# CorrosenseBoard_V4_2.net
KiCad netlist of a schematic drawn in Altium Designer
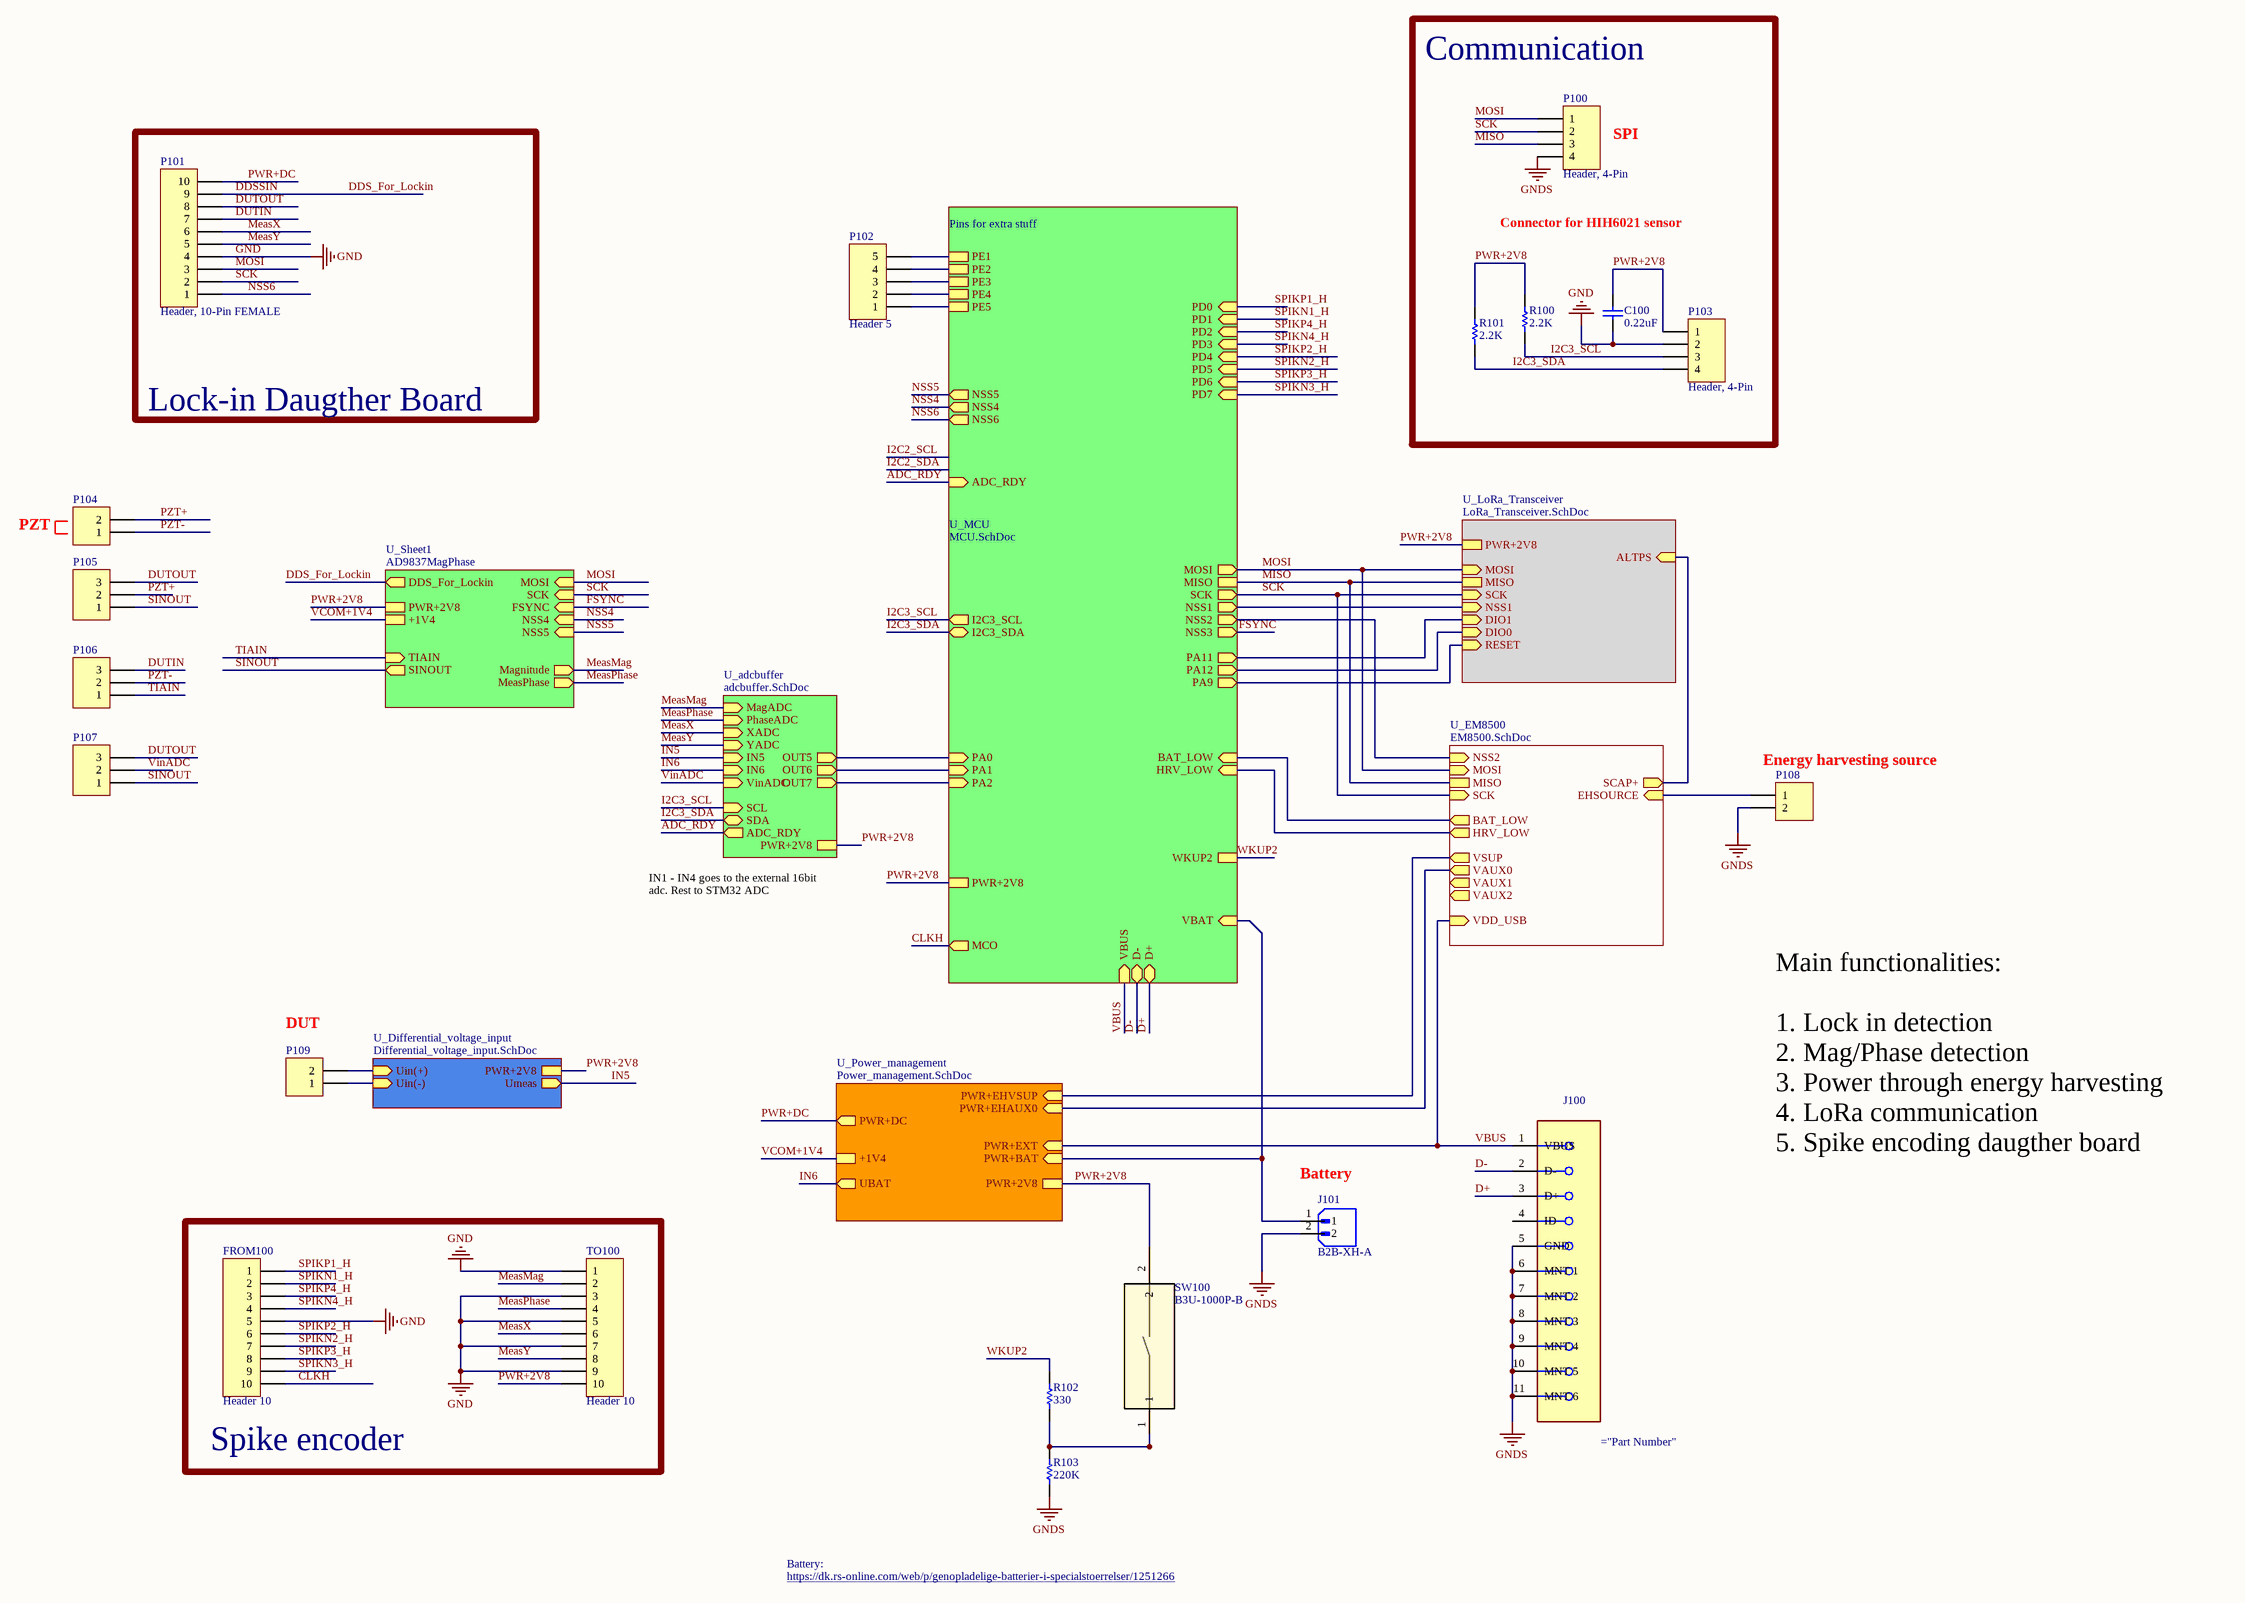
[diagram p0: CorrosenseBoard_V4.2.SchDoc]

(export (version "E")
  (design (tool "Eeschema 10.0.6"))
  (components
    (comp (ref "C100")
      (value "0.22uF")
      (footprint "1608[0603]")
      (description "CAP CER 25V X7R 0603")
      (fields (field (name "TOLERANCE") "±10%") (field (name "MANUFACTURER") "Murata Electronics"))
      (libsource (lib "Miscellaneous Devices") (part "Cap"))
    )
    (comp (ref "FROM100")
      (value "Header 10")
      (footprint "HDR1X10")
      (description "Header, 10-Pin")
      (fields
        (field (name "MANUFACTURER") "Wurth Elektronik")
        (field (name "MPN") "61301011121")
        (field (name "PUBLISHER") "Altium Limited")
      )
      (libsource (lib "") (part "Header 10_1"))
    )
    (comp (ref "J100")
      (value "0473460001")
      (footprint "Molex_0473460001_0")
      (description "USB Connectors MICRO USB B RECPT BTTM MOUNT ASSY")
      (fields (field (name "MANUFACTURER") "Molex"))
      (libsource (lib "Conn_Molex_0473460001_eec") (part "0473460001"))
    )
    (comp (ref "J101")
      (value "B2B-XH-A")
      (footprint "JST_B2B-XH-A")
      (description "B2B-XH-A(LF)(SN)")
      (fields
        (field (name "MF") "{'manufacturer': u'JST Sales America Inc.'}")
        (field (name "MANUFACTURER") "JST Commercial")
      )
      (libsource (lib "B2B-XH-A") (part "B2B-XH-A"))
    )
    (comp (ref "P100")
      (value "Header, 4-Pin")
      (footprint "HDR1X4")
      (fields
        (field (name "MANUFACTURER") "Würth Elektronik")
        (field (name "MPN") "61300411121")
        (field (name "PUBLISHER") "Altium Limited")
      )
      (libsource (lib "Miscellaneous Connectors") (part "Header 4"))
    )
    (comp (ref "P101")
      (value "Header, 10-Pin FEMALE")
      (footprint "HDR1X10")
      (description "Header, 10-Pin")
      (fields
        (field (name "MANUFACTURER") "Wurth Elektronik")
        (field (name "MPN") "61301011821")
        (field (name "PUBLISHER") "Altium Limited")
      )
      (libsource (lib "Miscellaneous Connectors") (part "Header 10"))
    )
    (comp (ref "P102")
      (value "Header 5")
      (footprint "HDR1X5")
      (description "Header, 5-Pin")
      (fields
        (field (name "MANUFACTURER") "Würth Elektronik")
        (field (name "MPN") "61300511121")
        (field (name "PUBLISHER") "Altium Limited")
      )
      (libsource (lib "Miscellaneous Connectors") (part "Header 5"))
    )
    (comp (ref "P103")
      (value "Header, 4-Pin")
      (footprint "HDR1X4")
      (fields
        (field (name "MANUFACTURER") "Würth Elektronik")
        (field (name "MPN") "61300411121")
        (field (name "PUBLISHER") "Altium Limited")
      )
      (libsource (lib "Miscellaneous Connectors") (part "Header 4"))
    )
    (comp (ref "P104")
      (value "Header, 2-Pin")
      (footprint "HDR1X2")
      (fields
        (field (name "MANUFACTURER") "Wurth Elektronik")
        (field (name "MPN") "61300211121")
        (field (name "PUBLISHER") "Altium Limited")
      )
      (libsource (lib "Miscellaneous Connectors") (part "Header 2"))
    )
    (comp (ref "P105")
      (value "Header, 3-Pin")
      (footprint "HDR1X3")
      (fields
        (field (name "MANUFACTURER") "Wurth Elektronik")
        (field (name "MPN") "61300311121")
        (field (name "PUBLISHER") "Altium Limited")
      )
      (libsource (lib "Miscellaneous Connectors") (part "Header 3"))
    )
    (comp (ref "P106")
      (value "Header, 3-Pin")
      (footprint "HDR1X3")
      (fields
        (field (name "MANUFACTURER") "Wurth Elektronik")
        (field (name "MPN") "61300311121")
        (field (name "PUBLISHER") "Altium Limited")
      )
      (libsource (lib "Miscellaneous Connectors") (part "Header 3"))
    )
    (comp (ref "P107")
      (value "Header, 3-Pin")
      (footprint "HDR1X3")
      (fields
        (field (name "MANUFACTURER") "Wurth Elektronik")
        (field (name "MPN") "61300311121")
        (field (name "PUBLISHER") "Altium Limited")
      )
      (libsource (lib "Miscellaneous Connectors") (part "Header 3"))
    )
    (comp (ref "P108")
      (value "Header, 2-Pin")
      (footprint "HDR1X2")
      (fields
        (field (name "MANUFACTURER") "Wurth Elektronik")
        (field (name "MPN") "61300211121")
        (field (name "PUBLISHER") "Altium Limited")
      )
      (libsource (lib "") (part "Header 2_1"))
    )
    (comp (ref "P109")
      (value "Header, 2-Pin")
      (footprint "HDR1X2")
      (fields
        (field (name "MANUFACTURER") "Wurth Elektronik")
        (field (name "MPN") "61300211121")
        (field (name "PUBLISHER") "Altium Limited")
      )
      (libsource (lib "Miscellaneous Connectors") (part "Header 2"))
    )
    (comp (ref "R100")
      (value "2.2K")
      (footprint "1608[0603]")
      (description "RES SMD 2% 1.5W 0603")
      (fields
        (field (name "TOLERANCE") "2%")
        (field (name "MANUFACTURER") "YAGEO")
        (field (name "PUBLISHER") "Altium Limited")
      )
      (libsource (lib "Miscellaneous Devices") (part "Res1"))
    )
    (comp (ref "R101")
      (value "2.2K")
      (footprint "1608[0603]")
      (description "1608[0603]")
      (fields
        (field (name "TOLERANCE") "2%")
        (field (name "MP") "-65°C ~ 155°C")
        (field (name "PUBLISHER") "Altium Limited")
      )
      (libsource (lib "Res1") (part "Res1"))
    )
    (comp (ref "R102")
      (value "330")
      (footprint "1608[0603]")
      (description "1608[0603]")
      (fields
        (field (name "TOLERANCE") "2%")
        (field (name "MP") "-65°C ~ 155°C")
        (field (name "PUBLISHER") "Altium Limited")
      )
      (libsource (lib "Res1") (part "Res1"))
    )
    (comp (ref "R103")
      (value "220K")
      (footprint "1608[0603]")
      (description "1608[0603]")
      (fields
        (field (name "TOLERANCE") "2%")
        (field (name "MP") "-65°C ~ 155°C")
        (field (name "PUBLISHER") "Altium Limited")
      )
      (libsource (lib "Res1") (part "Res1"))
    )
    (comp (ref "SW100")
      (value "B3U-1000P-B")
      (footprint "B3U-1000P-B")
      (description "No Description Available")
      (fields (field (name "MANUFACTURER") "Omron Electronics"))
      (libsource (lib "B3U-1000P-B") (part "B3U-1000P-B"))
    )
    (comp (ref "TO100")
      (value "Header 10")
      (footprint "HDR1X10")
      (description "Header, 10-Pin")
      (fields
        (field (name "MANUFACTURER") "Wurth Elektronik")
        (field (name "MPN") "61301011121")
        (field (name "PUBLISHER") "Altium Limited")
      )
      (libsource (lib "") (part "Header 10_2"))
    )
  )
  (nets
    (net (code "3") (name "/CLKH") (class "Default")
      (node (ref "FROM100") (pin "10") (pinfunction "10_10") (pintype "passive"))
    )
    (net (code "4") (name "/D+") (class "Default")
      (node (ref "J100") (pin "3") (pinfunction "D+_3") (pintype "passive"))
    )
    (net (code "5") (name "/D-") (class "Default")
      (node (ref "J100") (pin "2") (pinfunction "D-_2") (pintype "passive"))
    )
    (net (code "6") (name "/DDSSIN") (class "Default")
      (node (ref "P101") (pin "9") (pinfunction "9_9") (pintype "passive"))
    )
    (net (code "7") (name "/DUTIN") (class "Default")
      (node (ref "P101") (pin "7") (pinfunction "7_7") (pintype "passive"))
      (node (ref "P106") (pin "3") (pinfunction "3_3") (pintype "passive"))
    )
    (net (code "8") (name "/DUTOUT") (class "Default")
      (node (ref "P101") (pin "8") (pinfunction "8_8") (pintype "passive"))
      (node (ref "P105") (pin "3") (pinfunction "3_3") (pintype "passive"))
      (node (ref "P107") (pin "3") (pinfunction "3_3") (pintype "passive"))
    )
    (net (code "9") (name "/EHSOURCE") (class "Default")
      (node (ref "P108") (pin "1") (pinfunction "1_1") (pintype "passive"))
    )
    (net (code "14") (name "/I2C3_SCL") (class "Default")
      (node (ref "P103") (pin "3") (pinfunction "3_3") (pintype "passive"))
      (node (ref "R100") (pin "1") (pinfunction "1_1") (pintype "passive"))
    )
    (net (code "15") (name "/I2C3_SDA") (class "Default")
      (node (ref "P103") (pin "4") (pinfunction "4_4") (pintype "passive"))
      (node (ref "R101") (pin "1") (pinfunction "1_1") (pintype "passive"))
    )
    (net (code "18") (name "/MISO") (class "Default")
      (node (ref "P100") (pin "3") (pinfunction "3_3") (pintype "passive"))
    )
    (net (code "19") (name "/MOSI") (class "Default")
      (node (ref "P100") (pin "1") (pinfunction "1_1") (pintype "passive"))
      (node (ref "P101") (pin "3") (pinfunction "3_3") (pintype "passive"))
    )
    (net (code "20") (name "/MeasMag") (class "Default")
      (node (ref "TO100") (pin "2") (pinfunction "2_2") (pintype "passive"))
    )
    (net (code "21") (name "/MeasPhase") (class "Default")
      (node (ref "TO100") (pin "4") (pinfunction "4_4") (pintype "passive"))
    )
    (net (code "22") (name "/MeasX") (class "Default")
      (node (ref "P101") (pin "6") (pinfunction "6_6") (pintype "passive"))
      (node (ref "TO100") (pin "6") (pinfunction "6_6") (pintype "passive"))
    )
    (net (code "23") (name "/MeasY") (class "Default")
      (node (ref "P101") (pin "5") (pinfunction "5_5") (pintype "passive"))
      (node (ref "TO100") (pin "8") (pinfunction "8_8") (pintype "passive"))
    )
    (net (code "28") (name "/NSS6") (class "Default")
      (node (ref "P101") (pin "1") (pinfunction "1_1") (pintype "passive"))
    )
    (net (code "35") (name "/PE1") (class "Default")
      (node (ref "P102") (pin "5") (pinfunction "5_5") (pintype "passive"))
    )
    (net (code "36") (name "/PE2") (class "Default")
      (node (ref "P102") (pin "4") (pinfunction "4_4") (pintype "passive"))
    )
    (net (code "37") (name "/PE3") (class "Default")
      (node (ref "P102") (pin "3") (pinfunction "3_3") (pintype "passive"))
    )
    (net (code "38") (name "/PE4") (class "Default")
      (node (ref "P102") (pin "2") (pinfunction "2_2") (pintype "passive"))
    )
    (net (code "39") (name "/PE5") (class "Default")
      (node (ref "P102") (pin "1") (pinfunction "1_1") (pintype "passive"))
    )
    (net (code "40") (name "/PWR+2V8") (class "Default")
      (node (ref "C100") (pin "2") (pinfunction "2_2") (pintype "passive"))
      (node (ref "P103") (pin "1") (pinfunction "1_1") (pintype "passive"))
      (node (ref "R100") (pin "2") (pinfunction "2_2") (pintype "passive"))
      (node (ref "R101") (pin "2") (pinfunction "2_2") (pintype "passive"))
      (node (ref "SW100") (pin "2") (pinfunction "2_2") (pintype "passive"))
      (node (ref "TO100") (pin "10") (pinfunction "10_10") (pintype "passive"))
    )
    (net (code "41") (name "/PWR+BAT") (class "Default")
      (node (ref "J101") (pin "1") (pinfunction "1_1") (pintype "passive"))
    )
    (net (code "42") (name "/PWR+DC") (class "Default")
      (node (ref "P101") (pin "10") (pinfunction "10_10") (pintype "passive"))
    )
    (net (code "43") (name "/PZT+") (class "Default")
      (node (ref "P104") (pin "2") (pinfunction "2_2") (pintype "passive"))
      (node (ref "P105") (pin "2") (pinfunction "2_2") (pintype "passive"))
    )
    (net (code "44") (name "/PZT-") (class "Default")
      (node (ref "P104") (pin "1") (pinfunction "1_1") (pintype "passive"))
      (node (ref "P106") (pin "2") (pinfunction "2_2") (pintype "passive"))
    )
    (net (code "46") (name "/SCK") (class "Default")
      (node (ref "P100") (pin "2") (pinfunction "2_2") (pintype "passive"))
      (node (ref "P101") (pin "2") (pinfunction "2_2") (pintype "passive"))
    )
    (net (code "47") (name "/SINOUT") (class "Default")
      (node (ref "P105") (pin "1") (pinfunction "1_1") (pintype "passive"))
      (node (ref "P107") (pin "1") (pinfunction "1_1") (pintype "passive"))
    )
    (net (code "48") (name "/SPIKN1_H") (class "Default")
      (node (ref "FROM100") (pin "2") (pinfunction "2_2") (pintype "passive"))
    )
    (net (code "49") (name "/SPIKN2_H") (class "Default")
      (node (ref "FROM100") (pin "7") (pinfunction "7_7") (pintype "passive"))
    )
    (net (code "50") (name "/SPIKN3_H") (class "Default")
      (node (ref "FROM100") (pin "9") (pinfunction "9_9") (pintype "passive"))
    )
    (net (code "51") (name "/SPIKN4_H") (class "Default")
      (node (ref "FROM100") (pin "4") (pinfunction "4_4") (pintype "passive"))
    )
    (net (code "52") (name "/SPIKP1_H") (class "Default")
      (node (ref "FROM100") (pin "1") (pinfunction "1_1") (pintype "passive"))
    )
    (net (code "53") (name "/SPIKP2_H") (class "Default")
      (node (ref "FROM100") (pin "6") (pinfunction "6_6") (pintype "passive"))
    )
    (net (code "54") (name "/SPIKP3_H") (class "Default")
      (node (ref "FROM100") (pin "8") (pinfunction "8_8") (pintype "passive"))
    )
    (net (code "55") (name "/SPIKP4_H") (class "Default")
      (node (ref "FROM100") (pin "3") (pinfunction "3_3") (pintype "passive"))
    )
    (net (code "56") (name "/TIAIN") (class "Default")
      (node (ref "P106") (pin "1") (pinfunction "1_1") (pintype "passive"))
    )
    (net (code "57") (name "/Uin(+)") (class "Default")
      (node (ref "P109") (pin "2") (pinfunction "2_2") (pintype "passive"))
    )
    (net (code "58") (name "/Uin(-)") (class "Default")
      (node (ref "P109") (pin "1") (pinfunction "1_1") (pintype "passive"))
    )
    (net (code "62") (name "/VBUS") (class "Default")
      (node (ref "J100") (pin "1") (pinfunction "VBUS_1") (pintype "passive"))
    )
    (net (code "65") (name "/VinADC") (class "Default")
      (node (ref "P107") (pin "2") (pinfunction "2_2") (pintype "passive"))
    )
    (net (code "66") (name "/WKUP2") (class "Default")
      (node (ref "R102") (pin "2") (pinfunction "2_2") (pintype "passive"))
    )
    (net (code "67") (name "GND") (class "Default")
      (node (ref "C100") (pin "1") (pinfunction "1_1") (pintype "passive"))
      (node (ref "FROM100") (pin "5") (pinfunction "5_5") (pintype "passive"))
      (node (ref "P101") (pin "4") (pinfunction "4_4") (pintype "passive"))
      (node (ref "P103") (pin "2") (pinfunction "2_2") (pintype "passive"))
      (node (ref "TO100") (pin "1") (pinfunction "1_1") (pintype "passive"))
      (node (ref "TO100") (pin "3") (pinfunction "3_3") (pintype "passive"))
      (node (ref "TO100") (pin "5") (pinfunction "5_5") (pintype "passive"))
      (node (ref "TO100") (pin "7") (pinfunction "7_7") (pintype "passive"))
      (node (ref "TO100") (pin "9") (pinfunction "9_9") (pintype "passive"))
    )
    (net (code "68") (name "GNDS") (class "Default")
      (node (ref "J100") (pin "10") (pinfunction "MNT_5_10") (pintype "passive"))
      (node (ref "J100") (pin "11") (pinfunction "MNT_6_11") (pintype "passive"))
      (node (ref "J100") (pin "5") (pinfunction "GND_5") (pintype "passive"))
      (node (ref "J100") (pin "6") (pinfunction "MNT_1_6") (pintype "passive"))
      (node (ref "J100") (pin "7") (pinfunction "MNT_2_7") (pintype "passive"))
      (node (ref "J100") (pin "8") (pinfunction "MNT_3_8") (pintype "passive"))
      (node (ref "J100") (pin "9") (pinfunction "MNT_4_9") (pintype "passive"))
      (node (ref "J101") (pin "2") (pinfunction "2_2") (pintype "passive"))
      (node (ref "P100") (pin "4") (pinfunction "4_4") (pintype "passive"))
      (node (ref "P108") (pin "2") (pinfunction "2_2") (pintype "passive"))
      (node (ref "R103") (pin "1") (pinfunction "1_1") (pintype "passive"))
    )
    (net (code "69") (name "Net-(R102-Pad1)") (class "Default")
      (node (ref "R102") (pin "1") (pinfunction "1_1") (pintype "passive"))
      (node (ref "R103") (pin "2") (pinfunction "2_2") (pintype "passive"))
      (node (ref "SW100") (pin "1") (pinfunction "1_1") (pintype "passive"))
    )
    (net (code "70") (name "unconnected-(J100-ID-Pad4)") (class "Default")
      (node (ref "J100") (pin "4") (pinfunction "ID_4") (pintype "passive"))
    )
  )
)
